# repeater.net
KiCad netlist of a schematic drawn in EAGLE
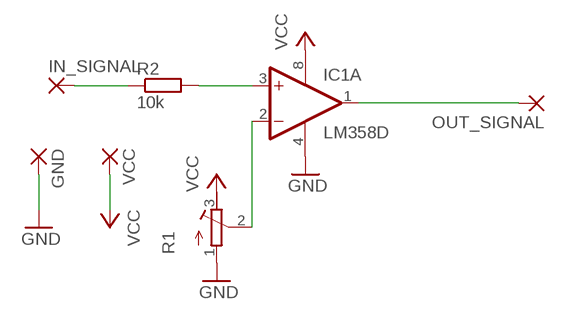
[diagram p0: schematic, sheet 1]

(export (version "E")
  (design (tool "Eeschema 10.0.6"))
  (components
    (comp (ref "GND")
      (value "SMD5")
      (footprint "eagle-import:SMD2,54-5,08")
      (libsource (lib "eagle-import") (part "SMD5"))
    )
    (comp (ref "IC1")
      (value "LM358D")
      (footprint "eagle-import:SO08")
      (libsource (lib "eagle-import") (part "LM358D"))
    )
    (comp (ref "IN_SIGNAL")
      (value "SMD5")
      (footprint "eagle-import:SMD2,54-5,08")
      (libsource (lib "eagle-import") (part "SMD5"))
    )
    (comp (ref "OUT_SIGNAL")
      (value "SMD5")
      (footprint "eagle-import:SMD2,54-5,08")
      (libsource (lib "eagle-import") (part "SMD5"))
    )
    (comp (ref "R1")
      (value "R-TRIMM3296W")
      (footprint "eagle-import:RTRIM3296W")
      (libsource (lib "eagle-import") (part "R-TRIMM3296W"))
    )
    (comp (ref "R2")
      (value "10k")
      (footprint "eagle-import:R0805")
      (libsource (lib "eagle-import") (part "R-EU_R0805"))
    )
    (comp (ref "VCC")
      (value "SMD5")
      (footprint "eagle-import:SMD2,54-5,08")
      (libsource (lib "eagle-import") (part "SMD5"))
    )
  )
  (nets
    (net (code "1") (name "GND") (class "Default")
      (node (ref "GND") (pin "1") (pinfunction "P_1") (pintype "passive"))
      (node (ref "IC1") (pin "4") (pinfunction "V-_4") (pintype "power_in"))
      (node (ref "R1") (pin "1") (pinfunction "A_1") (pintype "passive"))
    )
    (net (code "2") (name "Net-(IC1A-+IN)") (class "Default")
      (node (ref "IC1") (pin "3") (pinfunction "+IN_3") (pintype "input"))
      (node (ref "R2") (pin "2") (pinfunction "2_2") (pintype "passive"))
    )
    (net (code "3") (name "Net-(IC1A--IN)") (class "Default")
      (node (ref "IC1") (pin "2") (pinfunction "-IN_2") (pintype "input"))
      (node (ref "R1") (pin "2") (pinfunction "S_2") (pintype "passive"))
    )
    (net (code "4") (name "Net-(IC1A-OUT)") (class "Default")
      (node (ref "IC1") (pin "1") (pinfunction "OUT_1") (pintype "output"))
      (node (ref "OUT_SIGNAL") (pin "1") (pinfunction "P_1") (pintype "passive"))
    )
    (net (code "5") (name "Net-(IN_SIGNAL-P)") (class "Default")
      (node (ref "IN_SIGNAL") (pin "1") (pinfunction "P_1") (pintype "passive"))
      (node (ref "R2") (pin "1") (pinfunction "1_1") (pintype "passive"))
    )
    (net (code "6") (name "VCC") (class "Default")
      (node (ref "IC1") (pin "8") (pinfunction "V+_8") (pintype "power_in"))
      (node (ref "R1") (pin "3") (pinfunction "E_3") (pintype "passive"))
      (node (ref "VCC") (pin "1") (pinfunction "P_1") (pintype "passive"))
    )
  )
)
